# Antenna_Supervisor.net
KiCad netlist of a schematic drawn in Altium Designer
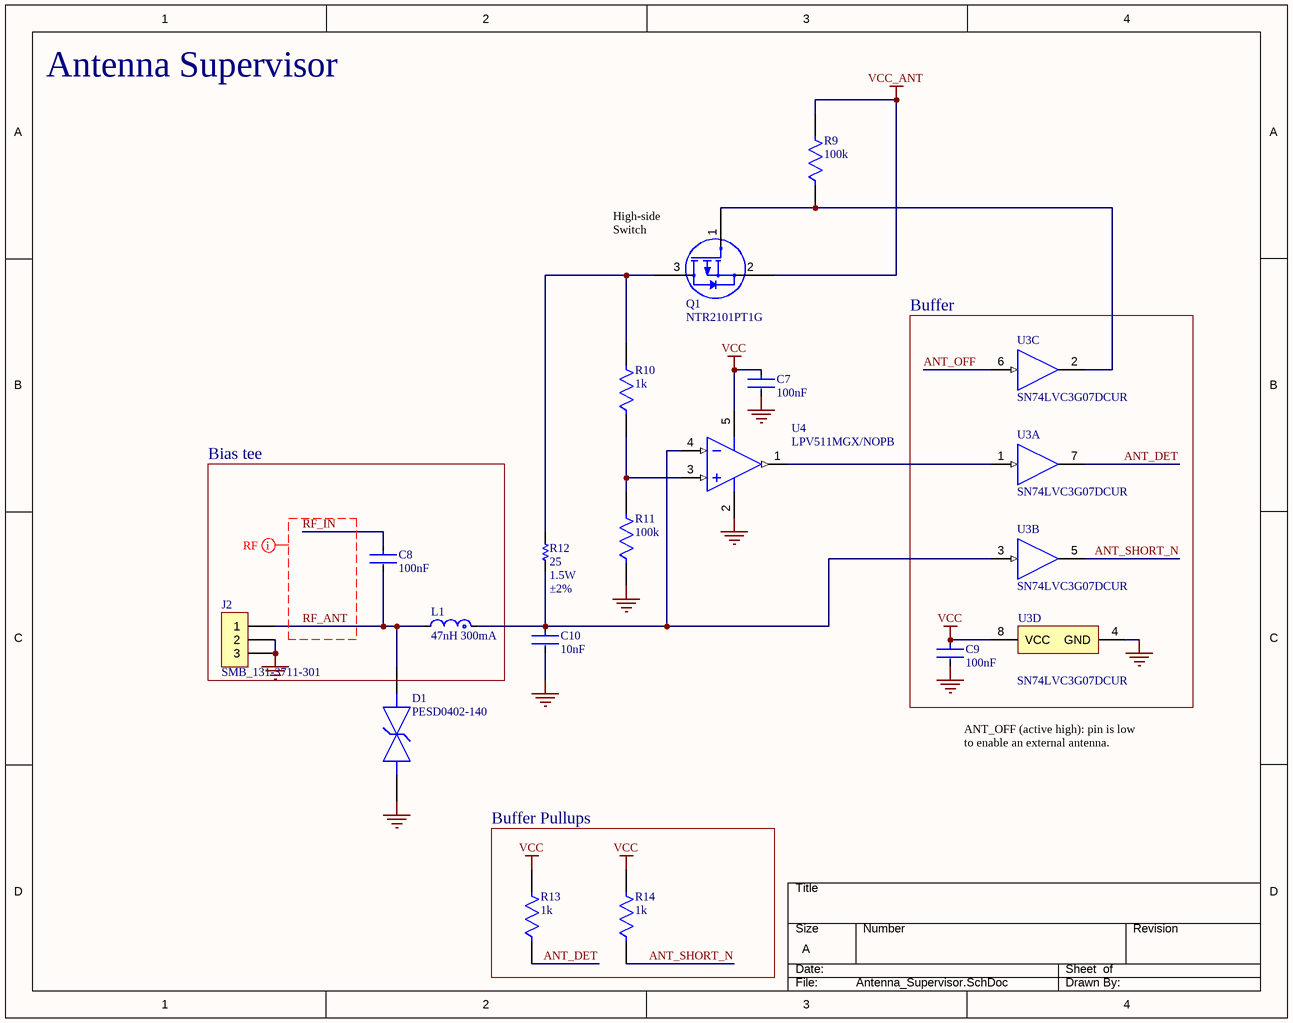
[diagram p0: Antenna_Supervisor.SchDoc]

(export (version "E")
  (design (tool "Eeschema 10.0.6"))
  (components
    (comp (ref "C7")
      (value "100nF")
      (footprint "FP-0402-L_1_0_0_05-W_0_5-IPC_B")
      (description "None")
      (fields (field (name "TOLERANCE") "10%"))
      (libsource (lib "Altium Content Vault") (part "b4654b650e69147ec39a6b967a45e02"))
    )
    (comp (ref "C8")
      (value "100nF")
      (footprint "FP-0402-L_1_0_0_05-W_0_5-IPC_B")
      (description "None")
      (fields (field (name "TOLERANCE") "10%"))
      (libsource (lib "Altium Content Vault") (part "b4654b650e69147ec39a6b967a45e02"))
    )
    (comp (ref "C9")
      (value "100nF")
      (footprint "FP-0402-L_1_0_0_05-W_0_5-IPC_B")
      (description "None")
      (fields (field (name "TOLERANCE") "10%"))
      (libsource (lib "Altium Content Vault") (part "b4654b650e69147ec39a6b967a45e02"))
    )
    (comp (ref "C10")
      (value "10nF")
      (footprint "FP-GRM033-0_03-IPC_B")
      (description "CAP CER 10000PF 16V X7R 0402")
      (fields (field (name "MANUFACTURER PART NUMBER") "CC0402KRX7R7BB103") (field (name "TOLERANCE") "0.1"))
      (libsource (lib "Altium Content Vault") (part "11868f565c42a9108669ba33697ecf6"))
    )
    (comp (ref "D1")
      (value "PESD0402-140")
      (footprint "FP-PESD0402-MFG")
      (description "TVS DIODE 14V 40V 0402")
      (fields
        (field (name "OCTOPART") "https://octopart.com/pesd0402-140-littelfuse-74215061")
        (field (name "MANUFACTURER") "Littelfuse Inc.")
      )
      (libsource (lib "Altium Content Vault") (part "edccc070dd5cba1f9372128faf3915e"))
    )
    (comp (ref "J2")
      (value "SMB_131-3711-301")
      (footprint "CONN_131-3711-301")
      (description "Rf Coaxial Board Mount Connector")
      (fields
        (field (name "MANUFACTURER") "Bel Cinch")
        (field (name "MANUFACTURER PART NUMBER") "131-3711-301")
      )
      (libsource (lib "MyLibrary") (part "CONN_131-3711-301"))
    )
    (comp (ref "L1")
      (value "47nH 300mA")
      (footprint "FP-LQG15HH_02-IPC_B")
      (description "Multilayer type RF Inductor 47nH ±5% 0.72Ω 300mA 0402")
      (fields (field (name "TOLERANCE") "5%"))
      (libsource (lib "Altium Content Vault") (part "4cc4b267dca4c8e51f7102f422741d8"))
    )
    (comp (ref "Q1")
      (value "onsemi_NTR2101PT1G")
      (footprint "SOT23_3pins_300x140x112")
      (description "MOSFET, P-CH, 8VDS, 3.7A ID, 0.052 OHM RDS(ON)@4.5VGS/3.5A, SOT-23-3")
      (fields
        (field (name "MANUFACTURER") "onsemi")
        (field (name "MANUFACTURER PART NUMBER") "NTR2101PT1G")
        (field (name "INTERNAL PART NUMBER") "839-00735-00")
      )
      (libsource (lib "RL Research Altium Server") (part "Transistor_MOS-P-CH_3pins_1G_1S_1D_DIO"))
    )
    (comp (ref "R9")
      (value "100k")
      (footprint "FP-RMCF0402-IPC_C")
      (description "100kΩ ±1% 0.063W 0402 Thick Film Chip Resistor AEC-Q200 compliant")
      (fields (field (name "TOLERANCE") "1%"))
      (libsource (lib "Altium Content Vault") (part "1029c3af85768c4190bb7ad29bc67b5"))
    )
    (comp (ref "R10")
      (value "1k")
      (footprint "FP-RMCF0402-MFG")
      (description "1kΩ ±1% 0.063W 0402 Thick Film Chip Resistor AEC-Q200 compliant")
      (fields (field (name "TOLERANCE") "1%"))
      (libsource (lib "Altium Content Vault") (part "1029c3af85768c4190bb7ad29bc67b5"))
    )
    (comp (ref "R11")
      (value "100k")
      (footprint "FP-RMCF0402-IPC_C")
      (description "100kΩ ±1% 0.063W 0402 Thick Film Chip Resistor AEC-Q200 compliant")
      (fields (field (name "TOLERANCE") "1%"))
      (libsource (lib "Altium Content Vault") (part "1029c3af85768c4190bb7ad29bc67b5"))
    )
    (comp (ref "R12")
      (value "Vishay_RCP0603W25R0GEB")
      (footprint "RESC1608X055N")
      (description "RES, 25 OHM, 2%, 1.5W, 150PPM/C, 0603")
      (fields
        (field (name "RESISTANCE") "25")
        (field (name "POWER (WATTS)") "1.5W")
        (field (name "TOLERANCE") "±2%")
        (field (name "INTERNAL PART NUMBER") "822-00198-00")
        (field (name "MANUFACTURER") "Vishay")
      )
      (libsource (lib "RL Research Altium Server") (part "Resistor_300mil"))
    )
    (comp (ref "R13")
      (value "1k")
      (footprint "FP-RMCF0402-MFG")
      (description "1kΩ ±1% 0.063W 0402 Thick Film Chip Resistor AEC-Q200 compliant")
      (fields (field (name "TOLERANCE") "1%"))
      (libsource (lib "Altium Content Vault") (part "1029c3af85768c4190bb7ad29bc67b5"))
    )
    (comp (ref "R14")
      (value "1k")
      (footprint "FP-RMCF0402-MFG")
      (description "1kΩ ±1% 0.063W 0402 Thick Film Chip Resistor AEC-Q200 compliant")
      (fields (field (name "TOLERANCE") "1%"))
      (libsource (lib "Altium Content Vault") (part "1029c3af85768c4190bb7ad29bc67b5"))
    )
    (comp (ref "U3")
      (value "SN74LVC3G07DCUR")
      (footprint "DCU0008A_N")
      (description "Triple Buffer/Driver With Open-Drain Output, DCU0008A, LARGE T&R")
      (fields
        (field (name "GENERIC PART NUMBER") "SN74LVC3G07")
        (field (name "MANUFACTURER") "Texas Instruments")
      )
      (libsource (lib "Altium Content Vault") (part "TI-SN74XXX3G0X-XX-8"))
    )
    (comp (ref "U4")
      (value "LPV511MGX/NOPB")
      (footprint "DCK0005A_N")
      (description "micropower Rail-to-Rail Input and Output Operational Amplifier, 5-pin SC-70, Pb-Free")
      (fields (field (name "MANUFACTURER") "Texas Instruments"))
      (libsource (lib "Altium Content Vault") (part "AMP-OPA-LM7121-5"))
    )
  )
  (nets
    (net (code "1") (name "/ANT_DET") (class "Default")
      (node (ref "R13") (pin "1") (pinfunction "1_1") (pintype "passive"))
      (node (ref "U3") (pin "7") (pinfunction "1Y_7") (pintype "open_collector"))
    )
    (net (code "2") (name "/ANT_OFF") (class "Default")
      (node (ref "U3") (pin "6") (pinfunction "3A_6") (pintype "input"))
    )
    (net (code "3") (name "/ANT_SHORT_N") (class "Default")
      (node (ref "R14") (pin "1") (pinfunction "1_1") (pintype "passive"))
      (node (ref "U3") (pin "5") (pinfunction "2Y_5") (pintype "open_collector"))
    )
    (net (code "4") (name "/RF_ANT") (class "Default")
      (node (ref "C8") (pin "2") (pinfunction "2_2") (pintype "passive"))
      (node (ref "D1") (pin "2") (pinfunction "2_2") (pintype "passive"))
      (node (ref "J2") (pin "1") (pinfunction "1_1") (pintype "passive"))
      (node (ref "L1") (pin "2") (pinfunction "2_2") (pintype "passive"))
    )
    (net (code "5") (name "/RF_IN") (class "Default")
      (node (ref "C8") (pin "1") (pinfunction "1_1") (pintype "passive"))
    )
    (net (code "6") (name "GND") (class "Default")
      (node (ref "C10") (pin "2") (pinfunction "2_2") (pintype "passive"))
      (node (ref "C7") (pin "2") (pinfunction "2_2") (pintype "passive"))
      (node (ref "C9") (pin "2") (pinfunction "2_2") (pintype "passive"))
      (node (ref "D1") (pin "1") (pinfunction "1_1") (pintype "passive"))
      (node (ref "J2") (pin "2") (pinfunction "2_2") (pintype "passive"))
      (node (ref "J2") (pin "3") (pinfunction "3_3") (pintype "passive"))
      (node (ref "R11") (pin "1") (pinfunction "1_1") (pintype "passive"))
      (node (ref "U3") (pin "4") (pinfunction "GND_4") (pintype "power_in"))
      (node (ref "U4") (pin "2") (pinfunction "V-_2") (pintype "power_in"))
    )
    (net (code "7") (name "Net-(Q1-D)") (class "Default")
      (node (ref "Q1") (pin "3") (pinfunction "D_3") (pintype "passive"))
      (node (ref "R10") (pin "2") (pinfunction "2_2") (pintype "passive"))
      (node (ref "R12") (pin "1") (pinfunction "1_1") (pintype "passive"))
    )
    (net (code "8") (name "Net-(Q1-G)") (class "Default")
      (node (ref "Q1") (pin "1") (pinfunction "G_1") (pintype "passive"))
      (node (ref "R9") (pin "1") (pinfunction "1_1") (pintype "passive"))
      (node (ref "U3") (pin "2") (pinfunction "3Y_2") (pintype "open_collector"))
    )
    (net (code "9") (name "Net-(U3A-1A)") (class "Default")
      (node (ref "U3") (pin "1") (pinfunction "1A_1") (pintype "input"))
      (node (ref "U4") (pin "1") (pinfunction "OUT_1") (pintype "output"))
    )
    (net (code "10") (name "Net-(U3B-2A)") (class "Default")
      (node (ref "C10") (pin "1") (pinfunction "1_1") (pintype "passive"))
      (node (ref "L1") (pin "1") (pinfunction "1_1") (pintype "passive"))
      (node (ref "R12") (pin "2") (pinfunction "2_2") (pintype "passive"))
      (node (ref "U3") (pin "3") (pinfunction "2A_3") (pintype "input"))
      (node (ref "U4") (pin "4") (pinfunction "IN-_4") (pintype "input"))
    )
    (net (code "11") (name "Net-(U4-IN+)") (class "Default")
      (node (ref "R10") (pin "1") (pinfunction "1_1") (pintype "passive"))
      (node (ref "R11") (pin "2") (pinfunction "2_2") (pintype "passive"))
      (node (ref "U4") (pin "3") (pinfunction "IN+_3") (pintype "input"))
    )
    (net (code "12") (name "VCC") (class "Default")
      (node (ref "C7") (pin "1") (pinfunction "1_1") (pintype "passive"))
      (node (ref "C9") (pin "1") (pinfunction "1_1") (pintype "passive"))
      (node (ref "R13") (pin "2") (pinfunction "2_2") (pintype "passive"))
      (node (ref "R14") (pin "2") (pinfunction "2_2") (pintype "passive"))
      (node (ref "U3") (pin "8") (pinfunction "VCC_8") (pintype "power_in"))
      (node (ref "U4") (pin "5") (pinfunction "V+_5") (pintype "power_in"))
    )
    (net (code "13") (name "VCC_ANT") (class "Default")
      (node (ref "Q1") (pin "2") (pinfunction "S_2") (pintype "passive"))
      (node (ref "R9") (pin "2") (pinfunction "2_2") (pintype "passive"))
    )
  )
)
